# BC28.net
KiCad netlist of a schematic drawn in Altium Designer
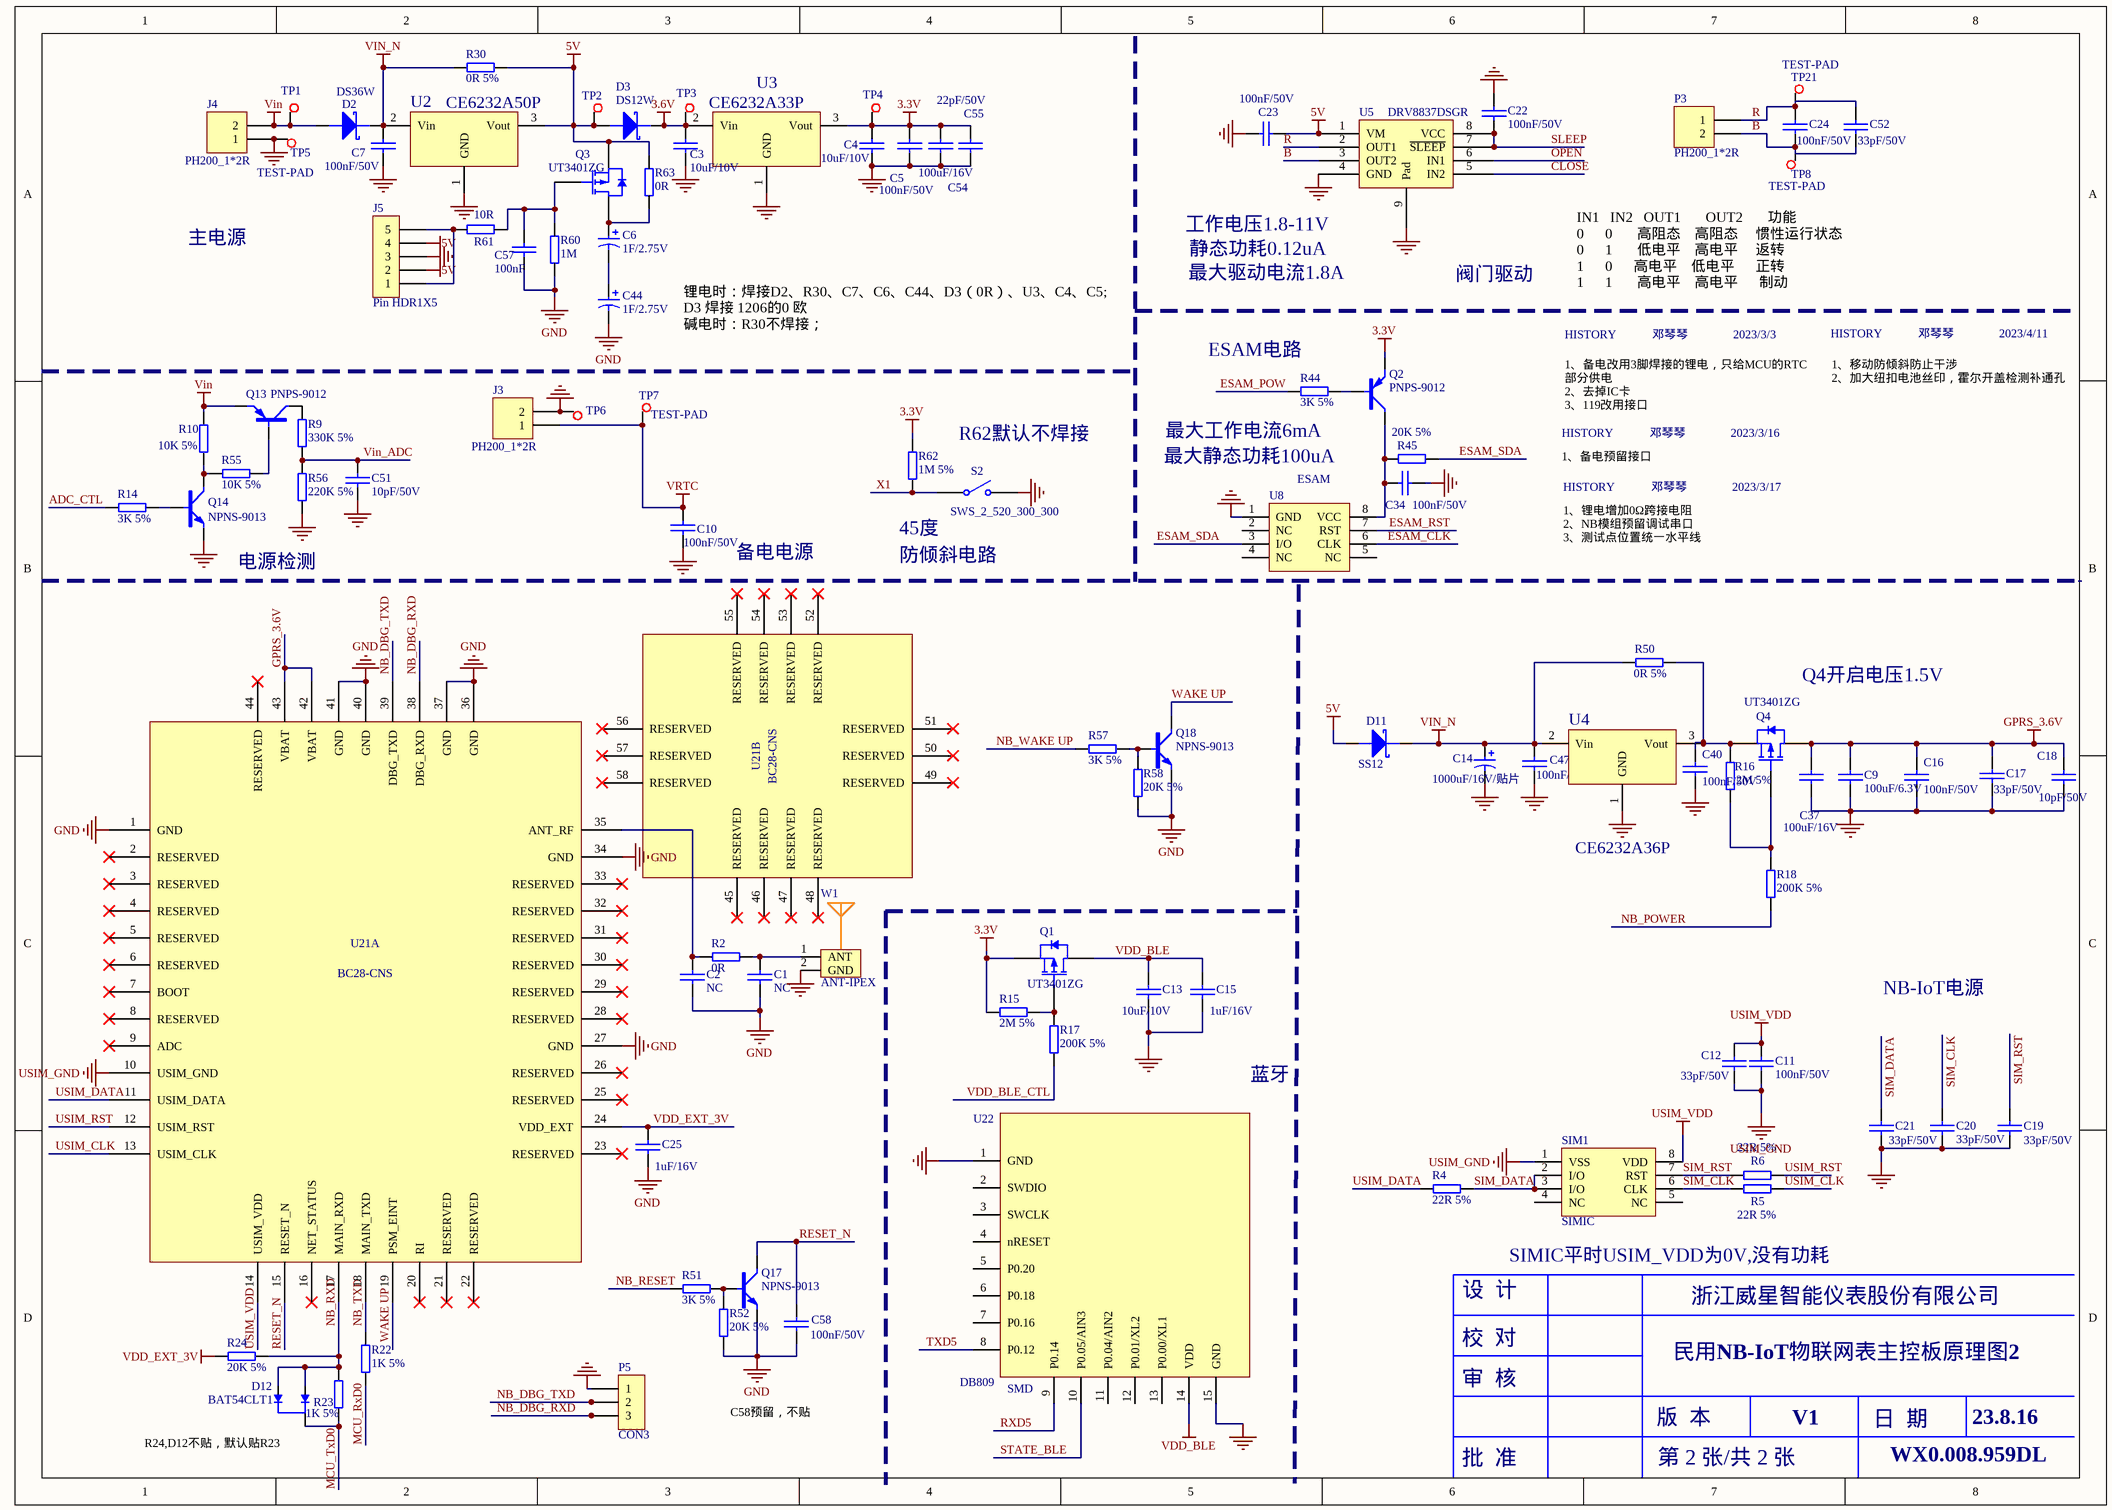
[diagram p0: BC28安全模组.SchDoc]

(export (version "E")
  (design (tool "Eeschema 10.0.6"))
  (components
    (comp (ref "C1")
      (value "NC")
      (footprint "CAP0603")
      (description "12P,50 V,±5%,0603,国巨,CC0603JRNPO9BN12")
      (fields (field (name "PART NUMBER") "101020103-0005"))
      (libsource (lib "Database_Libs2") (part "CC03JPO9_12P"))
    )
    (comp (ref "C2")
      (value "NC")
      (footprint "CAP0603")
      (description "12P,50 V,±5%,0603,国巨,CC0603JRNPO9BN12")
      (fields (field (name "PART NUMBER") "101020103-0005"))
      (libsource (lib "Database_Libs2") (part "CC03JPO9_12P"))
    )
    (comp (ref "C3")
      (value "10uF/10V")
      (footprint "CAP0603")
      (description "106pF,10 V,±10%,0603,村田,GRM188R61A106KE47D")
      (fields (field (name "PART NUMBER") "101020103-0026"))
      (libsource (lib "Database_Libs2") (part "CC03K5R6_10U"))
    )
    (comp (ref "C4")
      (value "10uF/10V")
      (footprint "CAP0603")
      (description "106pF,10 V,±10%,0603,村田,GRM188R61A106KE47D")
      (fields (field (name "PART NUMBER") "101020103-0026"))
      (libsource (lib "Database_Libs2") (part "CC03K5R6_10U"))
    )
    (comp (ref "C5")
      (value "100nF/50V")
      (footprint "CAP0603")
      (description "104pF,50 V,±10%,0603,国巨,CC0603KRX7R9BB104")
      (fields (field (name "PART NUMBER") "101020103-0021"))
      (libsource (lib "Database_Libs2") (part "CC03K7R9_100N"))
    )
    (comp (ref "C6")
      (value "1F/2.75V")
      (footprint "CAPPC_350_800_1600R")
      (description "1F,2.75 V,-20%~+20%,8mm*16mm,红宝石,2.7 DMC 1 M MY4 8X16")
      (fields (field (name "PART NUMBER") "1010202-0015"))
      (libsource (lib "Database_Libs2") (part "CALM3MRDMC_1F"))
    )
    (comp (ref "C7")
      (value "100nF/50V")
      (footprint "CAP0603")
      (description "104pF,50 V,±10%,0603,国巨,CC0603KRX7R9BB104")
      (fields (field (name "PART NUMBER") "101020103-0021"))
      (libsource (lib "Database_Libs2") (part "CC03K7R9_100N"))
    )
    (comp (ref "C9")
      (value "100uF/6.3V")
      (footprint "GRM1206")
      (description "100uF,6.3 V,±20%,1206,村田,GRM31CR60J107ME39L")
      (fields (field (name "PART NUMBER") "101020101-0020"))
      (libsource (lib "Database_Libs2") (part "CC06M5R5_107P"))
    )
    (comp (ref "C10")
      (value "100nF/50V")
      (footprint "CAP0603")
      (description "104pF,50 V,±10%,0603,国巨,CC0603KRX7R9BB104")
      (fields (field (name "PART NUMBER") "101020103-0021"))
      (libsource (lib "Database_Libs2") (part "CC03K7R9_100N"))
    )
    (comp (ref "C11")
      (value "100nF/50V")
      (footprint "CAP0603")
      (description "104pF,50 V,±10%,0603,国巨,CC0603KRX7R9BB104")
      (fields (field (name "PART NUMBER") "101020103-0021"))
      (libsource (lib "Database_Libs2") (part "CC03K7R9_100N"))
    )
    (comp (ref "C12")
      (value "33pF/50V")
      (footprint "CAP0603")
      (description "33pF,50 V,±10%,0603,国巨,CC0603KRNPO9BN33")
      (fields (field (name "PART NUMBER") "101020103-0027"))
      (libsource (lib "Database_Libs2") (part "CC03KPO9_33P"))
    )
    (comp (ref "C13")
      (value "10uF/10V")
      (footprint "CAP0603")
      (description "106pF,10 V,±10%,0603,村田,GRM188R61A106KE47D")
      (fields (field (name "PART NUMBER") "101020103-0026"))
      (libsource (lib "Database_Libs2") (part "CC03K5R6_10U"))
    )
    (comp (ref "C14")
      (value "1000uF/16V/贴片")
      (footprint "CAP-SMD_BD10.0-L10.3-W10.3-FD")
      (description "1000UF,16V,±20%,贴片10*10.2MM,深圳市三炎科电子科技有限公司,16V1000UF")
      (fields (field (name "PART NUMBER") "1010203-0026"))
      (libsource (lib "Database_Libs2") (part "CAL7MRZLH_1000U_R"))
    )
    (comp (ref "C15")
      (value "1uF/16V")
      (footprint "CAP0603")
      (description "105pF,16 V,±10%,0603,国巨,CC0603KRX7R7BB105")
      (fields (field (name "PART NUMBER") "101020103-0003"))
      (libsource (lib "Database_Libs2") (part "CC03K7R7_1U"))
    )
    (comp (ref "C16")
      (value "100nF/50V")
      (footprint "CAP0603")
      (description "104pF,50 V,±10%,0603,国巨,CC0603KRX7R9BB104")
      (fields (field (name "PART NUMBER") "101020103-0021"))
      (libsource (lib "Database_Libs2") (part "CC03K7R9_100N"))
    )
    (comp (ref "C17")
      (value "33pF/50V")
      (footprint "CAP0603")
      (description "33pF,50 V,±10%,0603,国巨,CC0603KRNPO9BN33")
      (fields (field (name "PART NUMBER") "101020103-0027"))
      (libsource (lib "Database_Libs2") (part "CC03KPO9_33P"))
    )
    (comp (ref "C18")
      (value "10pF/50V")
      (footprint "CAP0603")
      (description "10pF,50 V,±5%,0603,X7R,国巨,CC0603JRNPO9BN100")
      (fields (field (name "PART NUMBER") "101020103-0014"))
      (libsource (lib "Database_Libs2") (part "CC03JPO9_10P"))
    )
    (comp (ref "C19")
      (value "33pF/50V")
      (footprint "CAP0603")
      (description "33pF,50 V,±10%,0603,国巨,CC0603KRNPO9BN33")
      (fields (field (name "PART NUMBER") "101020103-0027"))
      (libsource (lib "Database_Libs2") (part "CC03KPO9_33P"))
    )
    (comp (ref "C20")
      (value "33pF/50V")
      (footprint "CAP0603")
      (description "33pF,50 V,±10%,0603,国巨,CC0603KRNPO9BN33")
      (fields (field (name "PART NUMBER") "101020103-0027"))
      (libsource (lib "Database_Libs2") (part "CC03KPO9_33P"))
    )
    (comp (ref "C21")
      (value "33pF/50V")
      (footprint "CAP0603")
      (description "33pF,50 V,±10%,0603,国巨,CC0603KRNPO9BN33")
      (fields (field (name "PART NUMBER") "101020103-0027"))
      (libsource (lib "Database_Libs2") (part "CC03KPO9_33P"))
    )
    (comp (ref "C22")
      (value "100nF/50V")
      (footprint "CAP0603")
      (description "104pF,50 V,±10%,0603,国巨,CC0603KRX7R9BB104")
      (fields (field (name "PART NUMBER") "101020103-0021"))
      (libsource (lib "Database_Libs2") (part "CC03K7R9_100N"))
    )
    (comp (ref "C23")
      (value "100nF/50V")
      (footprint "CAP0603")
      (description "104pF,50 V,±10%,0603,国巨,CC0603KRX7R9BB104")
      (fields (field (name "PART NUMBER") "101020103-0021"))
      (libsource (lib "Database_Libs2") (part "CC03K7R9_100N"))
    )
    (comp (ref "C24")
      (value "100nF/50V")
      (footprint "CAP0603")
      (description "104pF,50 V,±10%,0603,国巨,CC0603KRX7R9BB104")
      (fields (field (name "PART NUMBER") "101020103-0021"))
      (libsource (lib "Database_Libs2") (part "CC03K7R9_100N"))
    )
    (comp (ref "C25")
      (value "1uF/16V")
      (footprint "CAP0603")
      (description "105pF,16 V,±10%,0603,国巨,CC0603KRX7R7BB105")
      (fields (field (name "PART NUMBER") "101020103-0003"))
      (libsource (lib "Database_Libs2") (part "CC03K7R7_1U"))
    )
    (comp (ref "C34")
      (value "100nF/50V")
      (footprint "CAP0603")
      (description "104pF,50 V,±10%,0603,国巨,CC0603KRX7R9BB104")
      (fields (field (name "PART NUMBER") "101020103-0021"))
      (libsource (lib "Database_Libs2") (part "CC03K7R9_100N"))
    )
    (comp (ref "C37")
      (value "100uF/16V")
      (footprint "GRM31CR60J107ME39L")
      (libsource (lib "Database_Libs2") (part "CC06KPO7_106P"))
    )
    (comp (ref "C40")
      (value "100nF/50V")
      (footprint "CAP0603")
      (description "104pF,50 V,±10%,0603,国巨,CC0603KRX7R9BB104")
      (fields (field (name "PART NUMBER") "101020103-0021"))
      (libsource (lib "Database_Libs2") (part "CC03K7R9_100N"))
    )
    (comp (ref "C44")
      (value "1F/2.75V")
      (footprint "CAPPC_350_800_1600R")
      (description "1F,2.75 V,-20%~+20%,8mm*16mm,红宝石,2.7 DMC 1 M MY4 8X16")
      (fields (field (name "PART NUMBER") "1010202-0015"))
      (libsource (lib "Database_Libs2") (part "CALM3MRDMC_1F"))
    )
    (comp (ref "C47")
      (value "100nF/50V")
      (footprint "CAP0603")
      (description "104pF,50 V,±10%,0603,国巨,CC0603KRX7R9BB104")
      (fields (field (name "PART NUMBER") "101020103-0021"))
      (libsource (lib "Database_Libs2") (part "CC03K7R9_100N"))
    )
    (comp (ref "C51")
      (value "10pF/50V")
      (footprint "CAP0603")
      (description "10pF,50 V,±5%,0603,X7R,国巨,CC0603JRNPO9BN100")
      (fields (field (name "PART NUMBER") "101020103-0014"))
      (libsource (lib "Database_Libs2") (part "CC03JPO9_10P"))
    )
    (comp (ref "C52")
      (value "33pF/50V")
      (footprint "CAP0603")
      (description "104pF,50 V,±10%,0603,国巨,CC0603KRX7R9BB104")
      (fields (field (name "PART NUMBER") "101020103-0021"))
      (libsource (lib "Database_Libs2") (part "CC03K7R9_100N"))
    )
    (comp (ref "C54")
      (value "100uF/16V")
      (footprint "GRM31CR60J107ME39L")
      (description "100u,16 V,±10%,1206,国巨,CC1206KRNPO7BN106P")
      (libsource (lib "Database_Libs2") (part "CC06KPO7_106P"))
    )
    (comp (ref "C55")
      (value "22pF/50V")
      (footprint "CAP0603")
      (description "22pF,50 V,±5%,0603,国巨,CC0603JRNPO9BN22")
      (fields (field (name "PART NUMBER") "101020103-0009"))
      (libsource (lib "Database_Libs2") (part "CC03JPO9_22P"))
    )
    (comp (ref "C57")
      (value "100nF")
      (footprint "CAP0603")
      (description "无极性电容")
      (libsource (lib "CBB_Lib_SCH") (part "CAP"))
    )
    (comp (ref "C58")
      (value "100nF/50V")
      (footprint "CAP0603")
      (description "104pF,50 V,±10%,0603,国巨,CC0603KRX7R9BB104")
      (fields (field (name "PART NUMBER") "101020103-0021"))
      (libsource (lib "Database_Libs2") (part "CC03K7R9_100N"))
    )
    (comp (ref "D2")
      (value "DS36W")
      (footprint "SOD-123FL")
      (description "DS36W,SOD123-FL,3 A,42 V,60 V,浙江领晨科技有限公司,DS36W")
      (fields (field (name "PART NUMBER") "101040101-0055"))
      (libsource (lib "Database_Libs2") (part "02_DS12W"))
    )
    (comp (ref "D3")
      (value "DS12W")
      (footprint "SOD-123FL")
      (description "DS12W,SOD-123FL,1 A,0.55 V,20 V,领晨科技,DS12W")
      (fields (field (name "PART NUMBER") "101040101-0048"))
      (libsource (lib "Database_Libs2") (part "02_DS12W"))
    )
    (comp (ref "D11")
      (value "SS12")
      (footprint "DO-214AC")
      (description "SS12,DO-214AC,1 A,0.55 V,20 V,昶鑫,SS12")
      (fields (field (name "PART NUMBER") "101040101-0009"))
      (libsource (lib "Database_Libs2") (part "02_SS12"))
    )
    (comp (ref "D12")
      (value "BAT54CLT1")
      (footprint "SOT-23")
      (description "BAT54CLT1，SOT23-3,SOT23-3,0.2 A,0.8 V,30 V,安森美,BAT54CLT1")
      (fields (field (name "PART NUMBER") "101040101-0038"))
      (libsource (lib "Database_Libs2") (part "02_BAT54CLT1"))
    )
    (comp (ref "J3")
      (value "PH200_1*2R")
      (footprint "BAT-DIP-2")
      (description "2.0-2AW,直插弯座，2PIN，脚间距2mm，带防翘起,公头,单排,2.0-2AW;直插弯座，2PIN,脚间距2mm，带防翘起")
      (fields (field (name "PART NUMBER") "1010902-0105"))
      (libsource (lib "Database_Libs2") (part "PH200_1*2R"))
    )
    (comp (ref "J4")
      (value "PH200_1*2R")
      (footprint "PH200_1*2R_BAT")
      (description "2.0-2AW,直插弯座，2PIN，脚间距2mm，带防翘起,公头,单排,2.0-2AW;直插弯座，2PIN,脚间距2mm，带防翘起")
      (fields (field (name "PART NUMBER") "1010902-0105"))
      (libsource (lib "Database_Libs2") (part "PH200_1*2R"))
    )
    (comp (ref "J5")
      (value "Pin HDR1X5")
      (footprint "Pin HDR1X5/2.54mm-S")
      (libsource (lib "排针") (part "Pin HDR1X5"))
    )
    (comp (ref "P3")
      (value "PH200_1*2R")
      (footprint "PH200_1*2R")
      (description "2.0-2AW,直插弯座，2PIN，脚间距2mm，带防翘起,公头,单排,2.0-2AW;直插弯座，2PIN,脚间距2mm，带防翘起")
      (fields (field (name "PART NUMBER") "1010902-0105"))
      (libsource (lib "") (part "PH200_1*2R_1"))
    )
    (comp (ref "P5")
      (value "CON3")
      (footprint "SIP-3")
      (description "Connector")
      (libsource (lib "Miscellaneous Devices") (part "CON3"))
    )
    (comp (ref "Q1")
      (value "UT3401ZG")
      (footprint "SOT-23")
      (description "UT3401ZG,P-MOS,SOT-23,UTC,UT3401ZG")
      (fields (field (name "PART NUMBER") "101040201-0013"))
      (libsource (lib "Database_Libs2") (part "03_P-UT3401ZG"))
    )
    (comp (ref "Q2")
      (value "PNPS-9012")
      (footprint "SOT-23")
      (description "9012,PNP,SOT-23,JCET;长电,S9012")
      (fields (field (name "PART NUMBER") "101040201-0001"))
      (libsource (lib "Database_Libs2") (part "03_PNPS-9012"))
    )
    (comp (ref "Q3")
      (value "UT3401ZG")
      (footprint "SOT-23")
      (description "UT3401ZG,P-MOS,SOT-23,UTC,UT3401ZG")
      (fields (field (name "PART NUMBER") "101040201-0013"))
      (libsource (lib "Database_Libs2") (part "03_P-UT3401ZG"))
    )
    (comp (ref "Q4")
      (value "UT3401ZG")
      (footprint "SOT-23")
      (description "UT3401ZG,P-MOS,SOT-23,UTC,UT3401ZG")
      (fields (field (name "PART NUMBER") "101040201-0013"))
      (libsource (lib "Database_Libs2") (part "03_P-UT3401ZG"))
    )
    (comp (ref "Q13")
      (value "PNPS-9012")
      (footprint "SOT-23")
      (description "9012,PNP,SOT-23,JCET;长电,S9012")
      (fields (field (name "PART NUMBER") "101040201-0001"))
      (libsource (lib "Database_Libs2") (part "03_PNPS-9012"))
    )
    (comp (ref "Q14")
      (value "NPNS-9013")
      (footprint "SOT-23")
      (description "9013,NPN,SOT-23,长电,S9013")
      (fields (field (name "PART NUMBER") "101040201-0002"))
      (libsource (lib "Database_Libs2") (part "03_NPNS-9013"))
    )
    (comp (ref "Q17")
      (value "NPNS-9013")
      (footprint "SOT-23")
      (description "9013,NPN,SOT-23,长电,S9013")
      (fields (field (name "PART NUMBER") "101040201-0002"))
      (libsource (lib "Database_Libs2") (part "03_NPNS-9013"))
    )
    (comp (ref "Q18")
      (value "NPNS-9013")
      (footprint "SOT-23")
      (description "9013,NPN,SOT-23,长电,S9013")
      (fields (field (name "PART NUMBER") "101040201-0002"))
      (libsource (lib "Database_Libs2") (part "03_NPNS-9013"))
    )
    (comp (ref "R2")
      (value "0R")
      (footprint "RES0603")
      (fields (field (name "PART NUMBER") "101010103-0001"))
      (libsource (lib "Database_Libs2") (part "RC03J_0R"))
    )
    (comp (ref "R4")
      (value "22R 5%")
      (footprint "RES0603")
      (description "国巨,±5%,0603,,155 ℃,-55 ℃,RC0603JR-0722RL,无铅,200 ppm/℃,1/10W,,22欧")
      (fields (field (name "PART NUMBER") "101010103-0009"))
      (libsource (lib "Database_Libs2") (part "RC03J_22R"))
    )
    (comp (ref "R5")
      (value "22R 5%")
      (footprint "RES0603")
      (description "国巨,±5%,0603,,155 ℃,-55 ℃,RC0603JR-0722RL,无铅,200 ppm/℃,1/10W,,22欧")
      (fields (field (name "PART NUMBER") "101010103-0009"))
      (libsource (lib "Database_Libs2") (part "RC03J_22R"))
    )
    (comp (ref "R6")
      (value "22R 5%")
      (footprint "RES0603")
      (description "国巨,±5%,0603,,155 ℃,-55 ℃,RC0603JR-0722RL,无铅,200 ppm/℃,1/10W,,22欧")
      (fields (field (name "PART NUMBER") "101010103-0009"))
      (libsource (lib "Database_Libs2") (part "RC03J_22R"))
    )
    (comp (ref "R9")
      (value "330K 5%")
      (footprint "RES0603")
      (description "330K,±5%,1/10W,0603,国巨,RC0603JR-07330KL")
      (fields (field (name "PART NUMBER") "101010103-0066"))
      (libsource (lib "Database_Libs2") (part "RC03J_330K"))
    )
    (comp (ref "R10")
      (value "10K 5%")
      (footprint "RES0603")
      (description "国巨,±5%,0603,,155 ℃,-55 ℃,RC0603JR-0710KL,无铅,200 ppm/℃,1/10W,,10K")
      (fields (field (name "PART NUMBER") "101010103-0003"))
      (libsource (lib "Database_Libs2") (part "RC03J_10K"))
    )
    (comp (ref "R14")
      (value "3K 5%")
      (footprint "RES0603")
      (description "国巨,±5%,0603,,155 ℃,-55 ℃,RC0603JR-073KL,无铅,100 ppm/℃,1/10W,,3K")
      (fields (field (name "PART NUMBER") "101010103-0006"))
      (libsource (lib "Database_Libs2") (part "RC03J_3K"))
    )
    (comp (ref "R15")
      (value "2M 5%")
      (footprint "RES0603")
      (description "10K±5%,1/10W,0603")
      (fields (field (name "PART NUMBER") "101010103-0003"))
      (libsource (lib "Database_Libs1") (part "RC03JF_10K"))
    )
    (comp (ref "R16")
      (value "2M 5%")
      (footprint "RES0603")
      (description "国巨,±5%,0603,,155 ℃,-55 ℃,RC0603JR-072ML,含铅,100 ppm/℃,1/10W,,2M")
      (fields (field (name "PART NUMBER") "101010103-0025"))
      (libsource (lib "Database_Libs2") (part "RC03J_2M"))
    )
    (comp (ref "R17")
      (value "200K 5%")
      (footprint "RES0603")
      (description "10K±5%,1/10W,0603")
      (fields (field (name "PART NUMBER") "101010103-0003"))
      (libsource (lib "Database_Libs1") (part "RC03JF_10K"))
    )
    (comp (ref "R18")
      (value "200K 5%")
      (footprint "RES0603")
      (description "200K,±5%,1/10W,0603,国巨,RC0603JR-07200KL")
      (fields (field (name "PART NUMBER") "101010103-0034"))
      (libsource (lib "Database_Libs2") (part "RC03J_200K"))
    )
    (comp (ref "R22")
      (value "1K 5%")
      (footprint "RES0603")
      (description "220K,±5%,1/10W,0603,国巨,RC0603JR-07220KL")
      (fields (field (name "PART NUMBER") "101010103-0044"))
      (libsource (lib "Database_Libs2") (part "RC03J_220K"))
    )
    (comp (ref "R23")
      (value "1K 5%")
      (footprint "RES0603")
      (description "220K,±5%,1/10W,0603,国巨,RC0603JR-07220KL")
      (fields (field (name "PART NUMBER") "101010103-0044"))
      (libsource (lib "Database_Libs2") (part "RC03J_220K"))
    )
    (comp (ref "R24")
      (value "20K 5%")
      (footprint "RES0603")
      (description "国巨,±5%,0603,,155 ℃,-55 ℃,RC0603JR-0720KL,无铅,200 ppm/℃,1/10W,,20K")
      (fields (field (name "PART NUMBER") "101010103-0004"))
      (libsource (lib "Database_Libs2") (part "RC03J_20K"))
    )
    (comp (ref "R30")
      (value "0R 5%")
      (footprint "RES1206")
      (description "0Ω,±5%,1/4W,1206,国巨,RC1206JR-070RL")
      (fields (field (name "PART NUMBER") "101010101-0013"))
      (libsource (lib "Database_Libs2") (part "RC06J_0R"))
    )
    (comp (ref "R44")
      (value "3K 5%")
      (footprint "RES0603")
      (description "国巨,±5%,0603,,155 ℃,-55 ℃,RC0603JR-0710KL,无铅,200 ppm/℃,1/10W,,10K")
      (fields (field (name "PART NUMBER") "101010103-0003"))
      (libsource (lib "Database_Libs2") (part "RC03J_10K"))
    )
    (comp (ref "R45")
      (value "20K 5%")
      (footprint "RES0603")
      (description "国巨,±5%,0603,,155 ℃,-55 ℃,RC0603JR-0720KL,无铅,200 ppm/℃,1/10W,,20K")
      (fields (field (name "PART NUMBER") "101010103-0004"))
      (libsource (lib "Database_Libs2") (part "RC03J_20K"))
    )
    (comp (ref "R50")
      (value "0R 5%")
      (footprint "RES1206")
      (description "0Ω,±5%,1/4W,1206,国巨,RC1206JR-070RL")
      (fields (field (name "PART NUMBER") "101010101-0013"))
      (libsource (lib "Database_Libs2") (part "RC06J_0R"))
    )
    (comp (ref "R51")
      (value "3K 5%")
      (footprint "RES0603")
      (description "220K,±5%,1/10W,0603,国巨,RC0603JR-07220KL")
      (fields (field (name "PART NUMBER") "101010103-0044"))
      (libsource (lib "Database_Libs2") (part "RC03J_220K"))
    )
    (comp (ref "R52")
      (value "20K 5%")
      (footprint "RES0603")
      (description "220K,±5%,1/10W,0603,国巨,RC0603JR-07220KL")
      (fields (field (name "PART NUMBER") "101010103-0044"))
      (libsource (lib "Database_Libs2") (part "RC03J_220K"))
    )
    (comp (ref "R55")
      (value "10K 5%")
      (footprint "RES0603")
      (description "国巨,±5%,0603,,155 ℃,-55 ℃,RC0603JR-0710KL,无铅,200 ppm/℃,1/10W,,10K")
      (fields (field (name "PART NUMBER") "101010103-0003"))
      (libsource (lib "Database_Libs2") (part "RC03J_10K"))
    )
    (comp (ref "R56")
      (value "220K 5%")
      (footprint "RES0603")
      (description "220K,±5%,1/10W,0603,国巨,RC0603JR-07220KL")
      (fields (field (name "PART NUMBER") "101010103-0044"))
      (libsource (lib "Database_Libs2") (part "RC03J_220K"))
    )
    (comp (ref "R57")
      (value "3K 5%")
      (footprint "RES0603")
      (description "220K,±5%,1/10W,0603,国巨,RC0603JR-07220KL")
      (fields (field (name "PART NUMBER") "101010103-0044"))
      (libsource (lib "Database_Libs2") (part "RC03J_220K"))
    )
    (comp (ref "R58")
      (value "20K 5%")
      (footprint "RES0603")
      (description "220K,±5%,1/10W,0603,国巨,RC0603JR-07220KL")
      (fields (field (name "PART NUMBER") "101010103-0044"))
      (libsource (lib "Database_Libs2") (part "RC03J_220K"))
    )
    (comp (ref "R60")
      (value "1M")
      (footprint "Resistor_WX:RES0603")
      (libsource (lib "CBB_Lib_SCH") (part "RES"))
    )
    (comp (ref "R61") (value "10R") (footprint "RES0603") (libsource (lib "CBB_Lib_SCH") (part "RES")))
    (comp (ref "R62")
      (value "1M 5%")
      (footprint "RES0603")
      (description "国巨,±5%,0603,,155 ℃,-55 ℃,RC0603JR-071ML,无铅,200 ppm/℃,1/10W,,1M")
      (fields (field (name "PART NUMBER") "101010103-0002"))
      (libsource (lib "Database_Libs2") (part "RC03J_1M"))
    )
    (comp (ref "R63")
      (value "0R")
      (footprint "Resistor_WX:RES1206")
      (libsource (lib "CBB_Lib_SCH") (part "RES"))
    )
    (comp (ref "S2")
      (value "SWS_2_520_300_300")
      (footprint "SWS_2_520_300")
      (description "CSX-SEN-645B,垂直45°开关转换,3*5.2mm,360°任意方位倾斜检测,深圳市成晟科技有限公司")
      (fields (field (name "PART NUMBER") "1011001-0051"))
      (libsource (lib "Database_Libs2") (part "07_SWS_2_520_300_300"))
    )
    (comp (ref "SIM1")
      (value "SIMIC")
      (footprint "SIMIC")
      (description "SIMIC虚拟器件")
      (fields (field (name "PART NUMBER") "AD_XN_SIMIC_01"))
      (libsource (lib "Database_Libs2") (part "05_SIMIC"))
    )
    (comp (ref "TP1")
      (value "TEST-PAD")
      (footprint "TEST-PAD")
      (description "单面焊盘测试点")
      (fields (field (name "PART NUMBER") "AD_WXHJ_TEST-PAD_01"))
      (libsource (lib "Database_Libs2") (part "TEST-PAD"))
    )
    (comp (ref "TP2")
      (value "TEST-PAD")
      (footprint "TEST-PAD")
      (description "单面焊盘测试点")
      (fields (field (name "PART NUMBER") "AD_WXHJ_TEST-PAD_01"))
      (libsource (lib "Database_Libs2") (part "TEST-PAD"))
    )
    (comp (ref "TP3")
      (value "TEST-PAD")
      (footprint "TEST-PAD")
      (description "单面焊盘测试点")
      (fields (field (name "PART NUMBER") "AD_WXHJ_TEST-PAD_01"))
      (libsource (lib "Database_Libs2") (part "TEST-PAD"))
    )
    (comp (ref "TP4")
      (value "TEST-PAD")
      (footprint "TEST-PAD")
      (description "单面焊盘测试点")
      (fields (field (name "PART NUMBER") "AD_WXHJ_TEST-PAD_01"))
      (libsource (lib "Database_Libs2") (part "TEST-PAD"))
    )
    (comp (ref "TP5")
      (value "TEST-PAD")
      (footprint "TEST-PAD")
      (description "单面焊盘测试点")
      (fields (field (name "PART NUMBER") "AD_WXHJ_TEST-PAD_01"))
      (libsource (lib "Database_Libs2") (part "TEST-PAD"))
    )
    (comp (ref "TP6")
      (value "TEST-PAD")
      (footprint "TEST-PAD")
      (description "单面焊盘测试点")
      (fields (field (name "PART NUMBER") "AD_WXHJ_TEST-PAD_01"))
      (libsource (lib "Database_Libs2") (part "TEST-PAD"))
    )
    (comp (ref "TP7")
      (value "TEST-PAD")
      (footprint "TEST-PAD")
      (description "单面焊盘测试点")
      (fields (field (name "PART NUMBER") "AD_WXHJ_TEST-PAD_01"))
      (libsource (lib "Database_Libs2") (part "TEST-PAD"))
    )
    (comp (ref "TP8")
      (value "TEST-PAD")
      (footprint "TEST-PAD")
      (description "单面焊盘测试点")
      (fields (field (name "PART NUMBER") "AD_WXHJ_TEST-PAD_01"))
      (libsource (lib "Database_Libs2") (part "TEST-PAD"))
    )
    (comp (ref "TP21")
      (value "TEST-PAD")
      (footprint "TEST-PAD")
      (description "单面焊盘测试点")
      (fields (field (name "PART NUMBER") "AD_WXHJ_TEST-PAD_01"))
      (libsource (lib "Database_Libs2") (part "TEST-PAD"))
    )
    (comp (ref "U2")
      (value "CE6232A50P")
      (footprint "SOT-89")
      (fields (field (name "PART NUMBER") "1010503-0013"))
      (libsource (lib "Database_Libs2") (part "02_S-1206B50-U3"))
    )
    (comp (ref "U3")
      (value "CE6232A33P")
      (footprint "SOT-89")
      (fields (field (name "PART NUMBER") "1010503-0002"))
      (libsource (lib "Database_Libs2") (part "02_S-1206B33-U3T1G"))
    )
    (comp (ref "U4")
      (value "CE6232A36P")
      (footprint "SOT-89")
      (description "CE6232A36P,CE6232A36P,SOT89-3,8 V,1.8 V,0.11 V,3.6 V,600mA,0.8 uA,南京芯力微电子有限公司")
      (fields (field (name "PART NUMBER") "1010503-0031"))
      (libsource (lib "Database_Libs2") (part "02_CE6232A36P"))
    )
    (comp (ref "U5")
      (value "DRV8837DSGR")
      (footprint "S-PWSON-N8")
      (description "DRV8837DSGR,S-PWSON-N8,TI,DRV8837DSGR")
      (fields (field (name "PART NUMBER") "101050101-0060"))
      (libsource (lib "Database_Libs2") (part "07_DRV8837DSGR"))
    )
    (comp (ref "U8")
      (value "ESAM")
      (footprint "SOP-8")
      (description "ESAM虚拟器件")
      (fields (field (name "PART NUMBER") "AD_XN_ESAM_01"))
      (libsource (lib "Database_Libs2") (part "04_ESAM"))
    )
    (comp (ref "U21")
      (value "BC28-CNS")
      (footprint "BC28-CNS")
      (description "BC28-CNS Moudle 58Pin 15.8X17.7mm H2.2mm RO")
      (fields (field (name "MANUFACTURER") "Quectel"))
      (libsource (lib "Chip_WX") (part "BC28-CNS"))
    )
    (comp (ref "U22")
      (value "DB809")
      (footprint "DB809")
      (description "北高智蓝牙模块DB809")
      (fields (field (name "PART NUMBER") "1011402-0194") (field (name "SMD/DIP") "SMD"))
      (libsource (lib "Database_Libs2") (part "01_DB809"))
    )
    (comp (ref "W1")
      (value "ANT-IPEX")
      (footprint "ANT-IPEX")
      (description "IPEX，配GPRS天线转接线")
      (fields (field (name "PART NUMBER") "1010902-0053"))
      (libsource (lib "Database_Libs2") (part "IPEX"))
    )
  )
  (nets
    (net (code "1") (name "/ADC_CTL") (class "Default")
      (node (ref "R14") (pin "1") (pinfunction "1_1") (pintype "passive"))
    )
    (net (code "2") (name "/B") (class "Default")
      (node (ref "C24") (pin "2") (pinfunction "2_2") (pintype "passive"))
      (node (ref "C52") (pin "2") (pinfunction "2_2") (pintype "passive"))
      (node (ref "P3") (pin "2") (pinfunction "2_2") (pintype "passive"))
      (node (ref "TP8") (pin "1") (pinfunction "1_1") (pintype "passive"))
      (node (ref "U5") (pin "3") (pinfunction "OUT2_3") (pintype "passive"))
    )
    (net (code "3") (name "/CLOSE") (class "Default")
      (node (ref "U5") (pin "5") (pinfunction "IN2_5") (pintype "passive"))
    )
    (net (code "4") (name "/ESAM_CLK") (class "Default")
      (node (ref "U8") (pin "6") (pinfunction "CLK_6") (pintype "passive"))
    )
    (net (code "5") (name "/ESAM_POW") (class "Default")
      (node (ref "R44") (pin "1") (pinfunction "1_1") (pintype "passive"))
    )
    (net (code "6") (name "/ESAM_RST") (class "Default")
      (node (ref "U8") (pin "7") (pinfunction "RST_7") (pintype "passive"))
    )
    (net (code "7") (name "/ESAM_SDA") (class "Default")
      (node (ref "R45") (pin "2") (pinfunction "2_2") (pintype "passive"))
      (node (ref "U8") (pin "3") (pinfunction "I/O_3") (pintype "passive"))
    )
    (net (code "8") (name "/MCU_RxD0") (class "Default")
      (node (ref "R22") (pin "1") (pinfunction "1_1") (pintype "passive"))
    )
    (net (code "9") (name "/MCU_TxD0") (class "Default")
      (node (ref "D12") (pin "3") (pinfunction "C_3") (pintype "passive"))
      (node (ref "R23") (pin "2") (pinfunction "2_2") (pintype "passive"))
    )
    (net (code "10") (name "/NB_DBG_RXD") (class "Default")
      (node (ref "P5") (pin "3") (pinfunction "3_3") (pintype "passive"))
      (node (ref "U21") (pin "38") (pinfunction "DBG_RXD_38") (pintype "passive"))
    )
    (net (code "11") (name "/NB_DBG_TXD") (class "Default")
      (node (ref "P5") (pin "2") (pinfunction "2_2") (pintype "passive"))
      (node (ref "U21") (pin "39") (pinfunction "DBG_TXD_39") (pintype "passive"))
    )
    (net (code "12") (name "/NB_POWER") (class "Default")
      (node (ref "R18") (pin "1") (pinfunction "1_1") (pintype "passive"))
    )
    (net (code "13") (name "/NB_RESET") (class "Default")
      (node (ref "R51") (pin "1") (pinfunction "1_1") (pintype "passive"))
    )
    (net (code "14") (name "/NB_RXD") (class "Default")
      (node (ref "D12") (pin "1") (pinfunction "A_1") (pintype "passive"))
      (node (ref "D12") (pin "2") (pinfunction "A_2") (pintype "passive"))
      (node (ref "R23") (pin "1") (pinfunction "1_1") (pintype "passive"))
      (node (ref "R24") (pin "2") (pinfunction "2_2") (pintype "passive"))
      (node (ref "U21") (pin "17") (pinfunction "MAIN_RXD_17") (pintype "passive"))
    )
    (net (code "15") (name "/NB_TXD") (class "Default")
      (node (ref "R22") (pin "2") (pinfunction "2_2") (pintype "passive"))
      (node (ref "U21") (pin "18") (pinfunction "MAIN_TXD_18") (pintype "passive"))
    )
    (net (code "16") (name "/NB_WAKE UP") (class "Default")
      (node (ref "R57") (pin "1") (pinfunction "1_1") (pintype "passive"))
    )
    (net (code "17") (name "/OPEN") (class "Default")
      (node (ref "U5") (pin "6") (pinfunction "IN1_6") (pintype "passive"))
    )
    (net (code "18") (name "/R") (class "Default")
      (node (ref "C24") (pin "1") (pinfunction "1_1") (pintype "passive"))
      (node (ref "C52") (pin "1") (pinfunction "1_1") (pintype "passive"))
      (node (ref "P3") (pin "1") (pinfunction "1_1") (pintype "passive"))
      (node (ref "TP21") (pin "1") (pinfunction "1_1") (pintype "passive"))
      (node (ref "U5") (pin "2") (pinfunction "OUT1_2") (pintype "passive"))
    )
    (net (code "19") (name "/RESET_N") (class "Default")
      (node (ref "C58") (pin "1") (pinfunction "1_1") (pintype "passive"))
      (node (ref "Q17") (pin "3") (pinfunction "C_3") (pintype "passive"))
      (node (ref "U21") (pin "15") (pinfunction "RESET_N_15") (pintype "passive"))
    )
    (net (code "20") (name "/RXD5") (class "Default")
      (node (ref "U22") (pin "9") (pinfunction "P0.14_9") (pintype "passive"))
    )
    (net (code "21") (name "/SIM_CLK") (class "Default")
      (node (ref "C20") (pin "1") (pinfunction "1_1") (pintype "passive"))
      (node (ref "R5") (pin "1") (pinfunction "1_1") (pintype "passive"))
      (node (ref "SIM1") (pin "6") (pinfunction "CLK_6") (pintype "passive"))
    )
    (net (code "22") (name "/SIM_DATA") (class "Default")
      (node (ref "C21") (pin "1") (pinfunction "1_1") (pintype "passive"))
      (node (ref "R4") (pin "2") (pinfunction "2_2") (pintype "passive"))
      (node (ref "SIM1") (pin "2") (pinfunction "I/O_2") (pintype "passive"))
      (node (ref "SIM1") (pin "3") (pinfunction "I/O_3") (pintype "passive"))
    )
    (net (code "23") (name "/SIM_RST") (class "Default")
      (node (ref "C19") (pin "1") (pinfunction "1_1") (pintype "passive"))
      (node (ref "R6") (pin "1") (pinfunction "1_1") (pintype "passive"))
      (node (ref "SIM1") (pin "7") (pinfunction "RST_7") (pintype "passive"))
    )
    (net (code "24") (name "/SLEEP") (class "Default")
      (node (ref "C22") (pin "2") (pinfunction "2_2") (pintype "passive"))
      (node (ref "U5") (pin "7") (pinfunction "~{SLEEP}_7") (pintype "passive"))
      (node (ref "U5") (pin "8") (pinfunction "VCC_8") (pintype "passive"))
    )
    (net (code "25") (name "/STATE_BLE") (class "Default")
      (node (ref "U22") (pin "10") (pinfunction "P0.05/AIN3_10") (pintype "passive"))
    )
    (net (code "26") (name "/TXD5") (class "Default")
      (node (ref "U22") (pin "8") (pinfunction "P0.12_8") (pintype "passive"))
    )
    (net (code "27") (name "/USIM_CLK") (class "Default")
      (node (ref "R5") (pin "2") (pinfunction "2_2") (pintype "passive"))
      (node (ref "U21") (pin "13") (pinfunction "USIM_CLK_13") (pintype "passive"))
    )
    (net (code "28") (name "/USIM_DATA") (class "Default")
      (node (ref "R4") (pin "1") (pinfunction "1_1") (pintype "passive"))
      (node (ref "U21") (pin "11") (pinfunction "USIM_DATA_11") (pintype "passive"))
    )
    (net (code "29") (name "/USIM_RST") (class "Default")
      (node (ref "R6") (pin "2") (pinfunction "2_2") (pintype "passive"))
      (node (ref "U21") (pin "12") (pinfunction "USIM_RST_12") (pintype "passive"))
    )
    (net (code "30") (name "/VDD_BLE_CTL") (class "Default")
      (node (ref "R17") (pin "1") (pinfunction "1_1") (pintype "passive"))
    )
    (net (code "31") (name "/Vin_ADC") (class "Default")
      (node (ref "C51") (pin "2") (pinfunction "2_2") (pintype "passive"))
      (node (ref "R56") (pin "1") (pinfunction "1_1") (pintype "passive"))
      (node (ref "R9") (pin "2") (pinfunction "2_2") (pintype "passive"))
    )
    (net (code "32") (name "/WAKE UP") (class "Default")
      (node (ref "Q18") (pin "3") (pinfunction "C_3") (pintype "passive"))
      (node (ref "U21") (pin "19") (pinfunction "PSM_EINT_19") (pintype "passive"))
    )
    (net (code "33") (name "/X1") (class "Default")
      (node (ref "R62") (pin "1") (pinfunction "1_1") (pintype "passive"))
      (node (ref "S2") (pin "1") (pintype "passive"))
    )
    (net (code "34") (name "3.3V") (class "Default")
      (node (ref "C4") (pin "1") (pinfunction "1_1") (pintype "passive"))
      (node (ref "C5") (pin "1") (pinfunction "1_1") (pintype "passive"))
      (node (ref "C54") (pin "1") (pinfunction "1_1") (pintype "passive"))
      (node (ref "C55") (pin "1") (pinfunction "1_1") (pintype "passive"))
      (node (ref "Q1") (pin "2") (pinfunction "S_2") (pintype "passive"))
      (node (ref "Q2") (pin "2") (pinfunction "E_2") (pintype "passive"))
      (node (ref "R15") (pin "1") (pinfunction "1_1") (pintype "passive"))
      (node (ref "R62") (pin "2") (pinfunction "2_2") (pintype "passive"))
      (node (ref "TP4") (pin "1") (pinfunction "1_1") (pintype "passive"))
      (node (ref "U3") (pin "3") (pinfunction "Vout_3") (pintype "passive"))
    )
    (net (code "35") (name "3.6V") (class "Default")
      (node (ref "C3") (pin "1") (pinfunction "1_1") (pintype "passive"))
      (node (ref "D3") (pin "2") (pinfunction "2_2") (pintype "passive"))
      (node (ref "TP3") (pin "1") (pinfunction "1_1") (pintype "passive"))
      (node (ref "U3") (pin "2") (pinfunction "Vin_2") (pintype "passive"))
    )
    (net (code "36") (name "5V") (class "Default")
      (node (ref "C23") (pin "2") (pinfunction "2_2") (pintype "passive"))
      (node (ref "D11") (pin "1") (pinfunction "1_1") (pintype "passive"))
      (node (ref "D3") (pin "1") (pinfunction "1_1") (pintype "passive"))
      (node (ref "J5") (pin "2") (pinfunction "2_2") (pintype "passive"))
      (node (ref "J5") (pin "4") (pinfunction "4_4") (pintype "passive"))
      (node (ref "Q3") (pin "2") (pinfunction "S_2") (pintype "passive"))
      (node (ref "R30") (pin "2") (pinfunction "2_2") (pintype "passive"))
      (node (ref "R63") (pin "1") (pintype "passive"))
      (node (ref "TP2") (pin "1") (pinfunction "1_1") (pintype "passive"))
      (node (ref "U2") (pin "3") (pinfunction "Vout_3") (pintype "passive"))
      (node (ref "U5") (pin "1") (pinfunction "VM_1") (pintype "passive"))
    )
    (net (code "37") (name "GND") (class "Default")
      (node (ref "C1") (pin "1") (pinfunction "1_1") (pintype "passive"))
      (node (ref "C10") (pin "2") (pinfunction "2_2") (pintype "passive"))
      (node (ref "C13") (pin "2") (pinfunction "2_2") (pintype "passive"))
      (node (ref "C14") (pin "2") (pinfunction "2_2") (pintype "passive"))
      (node (ref "C15") (pin "2") (pinfunction "2_2") (pintype "passive"))
      (node (ref "C16") (pin "2") (pinfunction "2_2") (pintype "passive"))
      (node (ref "C17") (pin "2") (pinfunction "2_2") (pintype "passive"))
      (node (ref "C18") (pin "2") (pinfunction "2_2") (pintype "passive"))
      (node (ref "C19") (pin "2") (pinfunction "2_2") (pintype "passive"))
      (node (ref "C2") (pin "1") (pinfunction "1_1") (pintype "passive"))
      (node (ref "C20") (pin "2") (pinfunction "2_2") (pintype "passive"))
      (node (ref "C21") (pin "2") (pinfunction "2_2") (pintype "passive"))
      (node (ref "C22") (pin "1") (pinfunction "1_1") (pintype "passive"))
      (node (ref "C23") (pin "1") (pinfunction "1_1") (pintype "passive"))
      (node (ref "C25") (pin "2") (pinfunction "2_2") (pintype "passive"))
      (node (ref "C3") (pin "2") (pinfunction "2_2") (pintype "passive"))
      (node (ref "C34") (pin "2") (pinfunction "2_2") (pintype "passive"))
      (node (ref "C37") (pin "2") (pinfunction "2_2") (pintype "passive"))
      (node (ref "C4") (pin "2") (pinfunction "2_2") (pintype "passive"))
      (node (ref "C40") (pin "2") (pinfunction "2_2") (pintype "passive"))
      (node (ref "C44") (pin "2") (pinfunction "2_2") (pintype "passive"))
      (node (ref "C47") (pin "2") (pinfunction "2_2") (pintype "passive"))
      (node (ref "C5") (pin "2") (pinfunction "2_2") (pintype "passive"))
      (node (ref "C51") (pin "1") (pinfunction "1_1") (pintype "passive"))
      (node (ref "C54") (pin "2") (pinfunction "2_2") (pintype "passive"))
      (node (ref "C55") (pin "2") (pinfunction "2_2") (pintype "passive"))
      (node (ref "C57") (pin "2") (pintype "passive"))
      (node (ref "C58") (pin "2") (pinfunction "2_2") (pintype "passive"))
      (node (ref "C7") (pin "2") (pinfunction "2_2") (pintype "passive"))
      (node (ref "C9") (pin "2") (pinfunction "2_2") (pintype "passive"))
      (node (ref "J3") (pin "2") (pinfunction "2_2") (pintype "passive"))
      (node (ref "J4") (pin "1") (pinfunction "1_1") (pintype "passive"))
      (node (ref "J5") (pin "3") (pinfunction "3_3") (pintype "passive"))
      (node (ref "P5") (pin "1") (pinfunction "1_1") (pintype "passive"))
      (node (ref "Q14") (pin "2") (pinfunction "E_2") (pintype "passive"))
      (node (ref "Q17") (pin "2") (pinfunction "E_2") (pintype "passive"))
      (node (ref "Q18") (pin "2") (pinfunction "E_2") (pintype "passive"))
      (node (ref "R52") (pin "1") (pinfunction "1_1") (pintype "passive"))
      (node (ref "R56") (pin "2") (pinfunction "2_2") (pintype "passive"))
      (node (ref "R58") (pin "1") (pinfunction "1_1") (pintype "passive"))
      (node (ref "R60") (pin "2") (pintype "passive"))
      (node (ref "S2") (pin "2") (pintype "passive"))
      (node (ref "TP5") (pin "1") (pinfunction "1_1") (pintype "passive"))
      (node (ref "TP6") (pin "1") (pinfunction "1_1") (pintype "passive"))
      (node (ref "U2") (pin "1") (pinfunction "GND_1") (pintype "passive"))
      (node (ref "U21") (pin "1") (pinfunction "GND_1") (pintype "passive"))
      (node (ref "U21") (pin "27") (pinfunction "GND_27") (pintype "passive"))
      (node (ref "U21") (pin "34") (pinfunction "GND_34") (pintype "passive"))
      (node (ref "U21") (pin "36") (pinfunction "GND_36") (pintype "passive"))
      (node (ref "U21") (pin "37") (pinfunction "GND_37") (pintype "passive"))
      (node (ref "U21") (pin "40") (pinfunction "GND_40") (pintype "passive"))
      (node (ref "U21") (pin "41") (pinfunction "GND_41") (pintype "passive"))
      (node (ref "U22") (pin "1") (pinfunction "GND_1") (pintype "passive"))
      (node (ref "U22") (pin "15") (pinfunction "GND_15") (pintype "passive"))
      (node (ref "U3") (pin "1") (pinfunction "GND_1") (pintype "passive"))
      (node (ref "U4") (pin "1") (pinfunction "GND_1") (pintype "passive"))
      (node (ref "U5") (pin "4") (pinfunction "GND_4") (pintype "passive"))
      (node (ref "U5") (pin "9") (pinfunction "Pad_9") (pintype "passive"))
      (node (ref "U8") (pin "1") (pinfunction "GND_1") (pintype "passive"))
      (node (ref "W1") (pin "2") (pinfunction "GND_2") (pintype "passive"))
    )
    (net (code "38") (name "GPRS_3.6V") (class "Default")
      (node (ref "C16") (pin "1") (pinfunction "1_1") (pintype "passive"))
      (node (ref "C17") (pin "1") (pinfunction "1_1") (pintype "passive"))
      (node (ref "C18") (pin "1") (pinfunction "1_1") (pintype "passive"))
      (node (ref "C37") (pin "1") (pinfunction "1_1") (pintype "passive"))
      (node (ref "C9") (pin "1") (pinfunction "1_1") (pintype "passive"))
      (node (ref "Q4") (pin "3") (pinfunction "D_3") (pintype "passive"))
      (node (ref "U21") (pin "42") (pinfunction "VBAT_42") (pintype "passive"))
      (node (ref "U21") (pin "43") (pinfunction "VBAT_43") (pintype "passive"))
    )
    (net (code "39") (name "Net-(C44-Pad1)") (class "Default")
      (node (ref "C44") (pin "1") (pinfunction "1_1") (pintype "passive"))
      (node (ref "C6") (pin "2") (pinfunction "2_2") (pintype "passive"))
    )
    (net (code "40") (name "Net-(J5-Pad1)") (class "Default")
      (node (ref "J5") (pin "1") (pinfunction "1_1") (pintype "passive"))
      (node (ref "J5") (pin "5") (pinfunction "5_5") (pintype "passive"))
      (node (ref "R61") (pin "2") (pintype "passive"))
    )
    (net (code "41") (name "Net-(Q1-G)") (class "Default")
      (node (ref "Q1") (pin "1") (pinfunction "G_1") (pintype "passive"))
      (node (ref "R15") (pin "2") (pinfunction "2_2") (pintype "passive"))
      (node (ref "R17") (pin "2") (pinfunction "2_2") (pintype "passive"))
    )
    (net (code "42") (name "Net-(Q2-B)") (class "Default")
      (node (ref "Q2") (pin "1") (pinfunction "B_1") (pintype "passive"))
      (node (ref "R44") (pin "2") (pinfunction "2_2") (pintype "passive"))
    )
    (net (code "43") (name "Net-(Q2-C)") (class "Default")
      (node (ref "C34") (pin "1") (pinfunction "1_1") (pintype "passive"))
      (node (ref "Q2") (pin "3") (pinfunction "C_3") (pintype "passive"))
      (node (ref "R45") (pin "1") (pinfunction "1_1") (pintype "passive"))
      (node (ref "U8") (pin "8") (pinfunction "VCC_8") (pintype "passive"))
    )
    (net (code "44") (name "Net-(Q3-D)") (class "Default")
      (node (ref "C6") (pin "1") (pinfunction "1_1") (pintype "passive"))
      (node (ref "Q3") (pin "3") (pinfunction "D_3") (pintype "passive"))
      (node (ref "R63") (pin "2") (pintype "passive"))
    )
    (net (code "45") (name "Net-(Q3-G)") (class "Default")
      (node (ref "C57") (pin "1") (pintype "passive"))
      (node (ref "Q3") (pin "1") (pinfunction "G_1") (pintype "passive"))
      (node (ref "R60") (pin "1") (pintype "passive"))
      (node (ref "R61") (pin "1") (pintype "passive"))
    )
    (net (code "46") (name "Net-(Q4-G)") (class "Default")
      (node (ref "Q4") (pin "1") (pinfunction "G_1") (pintype "passive"))
      (node (ref "R16") (pin "1") (pinfunction "1_1") (pintype "passive"))
      (node (ref "R18") (pin "2") (pinfunction "2_2") (pintype "passive"))
    )
    (net (code "47") (name "Net-(Q4-S)") (class "Default")
      (node (ref "C40") (pin "1") (pinfunction "1_1") (pintype "passive"))
      (node (ref "Q4") (pin "2") (pinfunction "S_2") (pintype "passive"))
      (node (ref "R16") (pin "2") (pinfunction "2_2") (pintype "passive"))
      (node (ref "R50") (pin "2") (pinfunction "2_2") (pintype "passive"))
      (node (ref "U4") (pin "3") (pinfunction "Vout_3") (pintype "passive"))
    )
    (net (code "48") (name "Net-(Q13-B)") (class "Default")
      (node (ref "Q13") (pin "1") (pinfunction "B_1") (pintype "passive"))
      (node (ref "R55") (pin "2") (pinfunction "2_2") (pintype "passive"))
    )
    (net (code "49") (name "Net-(Q13-C)") (class "Default")
      (node (ref "Q13") (pin "3") (pinfunction "C_3") (pintype "passive"))
      (node (ref "R9") (pin "1") (pinfunction "1_1") (pintype "passive"))
    )
    (net (code "50") (name "Net-(Q14-B)") (class "Default")
      (node (ref "Q14") (pin "1") (pinfunction "B_1") (pintype "passive"))
      (node (ref "R14") (pin "2") (pinfunction "2_2") (pintype "passive"))
    )
    (net (code "51") (name "Net-(Q14-C)") (class "Default")
      (node (ref "Q14") (pin "3") (pinfunction "C_3") (pintype "passive"))
      (node (ref "R10") (pin "1") (pinfunction "1_1") (pintype "passive"))
      (node (ref "R55") (pin "1") (pinfunction "1_1") (pintype "passive"))
    )
    (net (code "52") (name "Net-(Q17-B)") (class "Default")
      (node (ref "Q17") (pin "1") (pinfunction "B_1") (pintype "passive"))
      (node (ref "R51") (pin "2") (pinfunction "2_2") (pintype "passive"))
      (node (ref "R52") (pin "2") (pinfunction "2_2") (pintype "passive"))
    )
    (net (code "53") (name "Net-(Q18-B)") (class "Default")
      (node (ref "Q18") (pin "1") (pinfunction "B_1") (pintype "passive"))
      (node (ref "R57") (pin "2") (pinfunction "2_2") (pintype "passive"))
      (node (ref "R58") (pin "2") (pinfunction "2_2") (pintype "passive"))
    )
    (net (code "54") (name "Net-(U21A-ANT_RF)") (class "Default")
      (node (ref "C2") (pin "2") (pinfunction "2_2") (pintype "passive"))
      (node (ref "R2") (pin "2") (pinfunction "2_2") (pintype "passive"))
      (node (ref "U21") (pin "35") (pinfunction "ANT_RF_35") (pintype "passive"))
    )
    (net (code "55") (name "Net-(W1-ANT)") (class "Default")
      (node (ref "C1") (pin "2") (pinfunction "2_2") (pintype "passive"))
      (node (ref "R2") (pin "1") (pinfunction "1_1") (pintype "passive"))
      (node (ref "W1") (pin "1") (pinfunction "ANT_1") (pintype "passive"))
    )
    (net (code "56") (name "USIM_GND") (class "Default")
      (node (ref "C11") (pin "2") (pinfunction "2_2") (pintype "passive"))
      (node (ref "C12") (pin "2") (pinfunction "2_2") (pintype "passive"))
      (node (ref "SIM1") (pin "1") (pinfunction "VSS_1") (pintype "passive"))
      (node (ref "U21") (pin "10") (pinfunction "USIM_GND_10") (pintype "passive"))
    )
    (net (code "57") (name "USIM_VDD") (class "Default")
      (node (ref "C11") (pin "1") (pinfunction "1_1") (pintype "passive"))
      (node (ref "C12") (pin "1") (pinfunction "1_1") (pintype "passive"))
      (node (ref "SIM1") (pin "8") (pinfunction "VDD_8") (pintype "passive"))
      (node (ref "U21") (pin "14") (pinfunction "USIM_VDD_14") (pintype "passive"))
    )
    (net (code "58") (name "VDD_BLE") (class "Default")
      (node (ref "C13") (pin "1") (pinfunction "1_1") (pintype "passive"))
      (node (ref "C15") (pin "1") (pinfunction "1_1") (pintype "passive"))
      (node (ref "Q1") (pin "3") (pinfunction "D_3") (pintype "passive"))
      (node (ref "U22") (pin "14") (pinfunction "VDD_14") (pintype "passive"))
    )
    (net (code "59") (name "VDD_EXT_3V") (class "Default")
      (node (ref "C25") (pin "1") (pinfunction "1_1") (pintype "passive"))
      (node (ref "R24") (pin "1") (pinfunction "1_1") (pintype "passive"))
      (node (ref "U21") (pin "24") (pinfunction "VDD_EXT_24") (pintype "passive"))
    )
    (net (code "60") (name "VIN_N") (class "Default")
      (node (ref "C14") (pin "1") (pinfunction "1_1") (pintype "passive"))
      (node (ref "C47") (pin "1") (pinfunction "1_1") (pintype "passive"))
      (node (ref "C7") (pin "1") (pinfunction "1_1") (pintype "passive"))
      (node (ref "D11") (pin "2") (pinfunction "2_2") (pintype "passive"))
      (node (ref "D2") (pin "2") (pinfunction "2_2") (pintype "passive"))
      (node (ref "R30") (pin "1") (pinfunction "1_1") (pintype "passive"))
      (node (ref "R50") (pin "1") (pinfunction "1_1") (pintype "passive"))
      (node (ref "U2") (pin "2") (pinfunction "Vin_2") (pintype "passive"))
      (node (ref "U4") (pin "2") (pinfunction "Vin_2") (pintype "passive"))
    )
    (net (code "61") (name "VRTC") (class "Default")
      (node (ref "C10") (pin "1") (pinfunction "1_1") (pintype "passive"))
      (node (ref "J3") (pin "1") (pinfunction "1_1") (pintype "passive"))
      (node (ref "TP7") (pin "1") (pinfunction "1_1") (pintype "passive"))
    )
    (net (code "62") (name "Vin") (class "Default")
      (node (ref "D2") (pin "1") (pinfunction "1_1") (pintype "passive"))
      (node (ref "J4") (pin "2") (pinfunction "2_2") (pintype "passive"))
      (node (ref "Q13") (pin "2") (pinfunction "E_2") (pintype "passive"))
      (node (ref "R10") (pin "2") (pinfunction "2_2") (pintype "passive"))
      (node (ref "TP1") (pin "1") (pinfunction "1_1") (pintype "passive"))
    )
    (net (code "63") (name "unconnected-(SIM1-NC-Pad4)") (class "Default")
      (node (ref "SIM1") (pin "4") (pinfunction "NC_4") (pintype "passive"))
    )
    (net (code "64") (name "unconnected-(SIM1-NC-Pad5)") (class "Default")
      (node (ref "SIM1") (pin "5") (pinfunction "NC_5") (pintype "passive"))
    )
    (net (code "65") (name "unconnected-(U8-NC-Pad2)") (class "Default")
      (node (ref "U8") (pin "2") (pinfunction "NC_2") (pintype "passive"))
    )
    (net (code "66") (name "unconnected-(U8-NC-Pad4)") (class "Default")
      (node (ref "U8") (pin "4") (pinfunction "NC_4") (pintype "passive"))
    )
    (net (code "67") (name "unconnected-(U8-NC-Pad5)") (class "Default")
      (node (ref "U8") (pin "5") (pinfunction "NC_5") (pintype "passive"))
    )
    (net (code "68") (name "unconnected-(U21A-ADC-Pad9)") (class "Default")
      (node (ref "U21") (pin "9") (pinfunction "ADC_9") (pintype "passive+no_connect"))
    )
    (net (code "69") (name "unconnected-(U21A-BOOT-Pad7)") (class "Default")
      (node (ref "U21") (pin "7") (pinfunction "BOOT_7") (pintype "passive+no_connect"))
    )
    (net (code "70") (name "unconnected-(U21A-NET_STATUS-Pad16)") (class "Default")
      (node (ref "U21") (pin "16") (pinfunction "NET_STATUS_16") (pintype "passive+no_connect"))
    )
    (net (code "71") (name "unconnected-(U21A-RESERVED-Pad2)") (class "Default")
      (node (ref "U21") (pin "2") (pinfunction "RESERVED_2") (pintype "passive+no_connect"))
    )
    (net (code "72") (name "unconnected-(U21A-RESERVED-Pad3)") (class "Default")
      (node (ref "U21") (pin "3") (pinfunction "RESERVED_3") (pintype "passive+no_connect"))
    )
    (net (code "73") (name "unconnected-(U21A-RESERVED-Pad4)") (class "Default")
      (node (ref "U21") (pin "4") (pinfunction "RESERVED_4") (pintype "passive+no_connect"))
    )
    (net (code "74") (name "unconnected-(U21A-RESERVED-Pad5)") (class "Default")
      (node (ref "U21") (pin "5") (pinfunction "RESERVED_5") (pintype "passive+no_connect"))
    )
    (net (code "75") (name "unconnected-(U21A-RESERVED-Pad6)") (class "Default")
      (node (ref "U21") (pin "6") (pinfunction "RESERVED_6") (pintype "passive+no_connect"))
    )
    (net (code "76") (name "unconnected-(U21A-RESERVED-Pad8)") (class "Default")
      (node (ref "U21") (pin "8") (pinfunction "RESERVED_8") (pintype "passive+no_connect"))
    )
    (net (code "77") (name "unconnected-(U21A-RESERVED-Pad21)") (class "Default")
      (node (ref "U21") (pin "21") (pinfunction "RESERVED_21") (pintype "passive+no_connect"))
    )
    (net (code "78") (name "unconnected-(U21A-RESERVED-Pad22)") (class "Default")
      (node (ref "U21") (pin "22") (pinfunction "RESERVED_22") (pintype "passive+no_connect"))
    )
    (net (code "79") (name "unconnected-(U21A-RESERVED-Pad23)") (class "Default")
      (node (ref "U21") (pin "23") (pinfunction "RESERVED_23") (pintype "passive+no_connect"))
    )
    (net (code "80") (name "unconnected-(U21A-RESERVED-Pad25)") (class "Default")
      (node (ref "U21") (pin "25") (pinfunction "RESERVED_25") (pintype "passive+no_connect"))
    )
    (net (code "81") (name "unconnected-(U21A-RESERVED-Pad26)") (class "Default")
      (node (ref "U21") (pin "26") (pinfunction "RESERVED_26") (pintype "passive+no_connect"))
    )
    (net (code "82") (name "unconnected-(U21A-RESERVED-Pad28)") (class "Default")
      (node (ref "U21") (pin "28") (pinfunction "RESERVED_28") (pintype "passive+no_connect"))
    )
    (net (code "83") (name "unconnected-(U21A-RESERVED-Pad29)") (class "Default")
      (node (ref "U21") (pin "29") (pinfunction "RESERVED_29") (pintype "passive+no_connect"))
    )
    (net (code "84") (name "unconnected-(U21A-RESERVED-Pad30)") (class "Default")
      (node (ref "U21") (pin "30") (pinfunction "RESERVED_30") (pintype "passive+no_connect"))
    )
    (net (code "85") (name "unconnected-(U21A-RESERVED-Pad31)") (class "Default")
      (node (ref "U21") (pin "31") (pinfunction "RESERVED_31") (pintype "passive+no_connect"))
    )
    (net (code "86") (name "unconnected-(U21A-RESERVED-Pad32)") (class "Default")
      (node (ref "U21") (pin "32") (pinfunction "RESERVED_32") (pintype "passive+no_connect"))
    )
    (net (code "87") (name "unconnected-(U21A-RESERVED-Pad33)") (class "Default")
      (node (ref "U21") (pin "33") (pinfunction "RESERVED_33") (pintype "passive+no_connect"))
    )
    (net (code "88") (name "unconnected-(U21A-RESERVED-Pad44)") (class "Default")
      (node (ref "U21") (pin "44") (pinfunction "RESERVED_44") (pintype "passive+no_connect"))
    )
    (net (code "89") (name "unconnected-(U21A-RI-Pad20)") (class "Default")
      (node (ref "U21") (pin "20") (pinfunction "RI_20") (pintype "passive+no_connect"))
    )
    (net (code "90") (name "unconnected-(U21B-RESERVED-Pad45)") (class "Default")
      (node (ref "U21") (pin "45") (pinfunction "RESERVED_45") (pintype "passive+no_connect"))
    )
    (net (code "91") (name "unconnected-(U21B-RESERVED-Pad46)") (class "Default")
      (node (ref "U21") (pin "46") (pinfunction "RESERVED_46") (pintype "passive+no_connect"))
    )
    (net (code "92") (name "unconnected-(U21B-RESERVED-Pad47)") (class "Default")
      (node (ref "U21") (pin "47") (pinfunction "RESERVED_47") (pintype "passive+no_connect"))
    )
    (net (code "93") (name "unconnected-(U21B-RESERVED-Pad48)") (class "Default")
      (node (ref "U21") (pin "48") (pinfunction "RESERVED_48") (pintype "passive+no_connect"))
    )
    (net (code "94") (name "unconnected-(U21B-RESERVED-Pad49)") (class "Default")
      (node (ref "U21") (pin "49") (pinfunction "RESERVED_49") (pintype "passive+no_connect"))
    )
    (net (code "95") (name "unconnected-(U21B-RESERVED-Pad50)") (class "Default")
      (node (ref "U21") (pin "50") (pinfunction "RESERVED_50") (pintype "passive+no_connect"))
    )
    (net (code "96") (name "unconnected-(U21B-RESERVED-Pad51)") (class "Default")
      (node (ref "U21") (pin "51") (pinfunction "RESERVED_51") (pintype "passive+no_connect"))
    )
    (net (code "97") (name "unconnected-(U21B-RESERVED-Pad52)") (class "Default")
      (node (ref "U21") (pin "52") (pinfunction "RESERVED_52") (pintype "passive+no_connect"))
    )
    (net (code "98") (name "unconnected-(U21B-RESERVED-Pad53)") (class "Default")
      (node (ref "U21") (pin "53") (pinfunction "RESERVED_53") (pintype "passive+no_connect"))
    )
    (net (code "99") (name "unconnected-(U21B-RESERVED-Pad54)") (class "Default")
      (node (ref "U21") (pin "54") (pinfunction "RESERVED_54") (pintype "passive+no_connect"))
    )
    (net (code "100") (name "unconnected-(U21B-RESERVED-Pad55)") (class "Default")
      (node (ref "U21") (pin "55") (pinfunction "RESERVED_55") (pintype "passive+no_connect"))
    )
    (net (code "101") (name "unconnected-(U21B-RESERVED-Pad56)") (class "Default")
      (node (ref "U21") (pin "56") (pinfunction "RESERVED_56") (pintype "passive+no_connect"))
    )
    (net (code "102") (name "unconnected-(U21B-RESERVED-Pad57)") (class "Default")
      (node (ref "U21") (pin "57") (pinfunction "RESERVED_57") (pintype "passive+no_connect"))
    )
    (net (code "103") (name "unconnected-(U21B-RESERVED-Pad58)") (class "Default")
      (node (ref "U21") (pin "58") (pinfunction "RESERVED_58") (pintype "passive+no_connect"))
    )
    (net (code "104") (name "unconnected-(U22-P0.00{slash}XL1-Pad13)") (class "Default")
      (node (ref "U22") (pin "13") (pinfunction "P0.00/XL1_13") (pintype "passive"))
    )
    (net (code "105") (name "unconnected-(U22-P0.01{slash}XL2-Pad12)") (class "Default")
      (node (ref "U22") (pin "12") (pinfunction "P0.01/XL2_12") (pintype "passive"))
    )
    (net (code "106") (name "unconnected-(U22-P0.04{slash}AIN2-Pad11)") (class "Default")
      (node (ref "U22") (pin "11") (pinfunction "P0.04/AIN2_11") (pintype "passive"))
    )
    (net (code "107") (name "unconnected-(U22-P0.16-Pad7)") (class "Default")
      (node (ref "U22") (pin "7") (pinfunction "P0.16_7") (pintype "passive"))
    )
    (net (code "108") (name "unconnected-(U22-P0.18-Pad6)") (class "Default")
      (node (ref "U22") (pin "6") (pinfunction "P0.18_6") (pintype "passive"))
    )
    (net (code "109") (name "unconnected-(U22-P0.20-Pad5)") (class "Default")
      (node (ref "U22") (pin "5") (pinfunction "P0.20_5") (pintype "passive"))
    )
    (net (code "110") (name "unconnected-(U22-SWCLK-Pad3)") (class "Default")
      (node (ref "U22") (pin "3") (pinfunction "SWCLK_3") (pintype "passive"))
    )
    (net (code "111") (name "unconnected-(U22-SWDIO-Pad2)") (class "Default")
      (node (ref "U22") (pin "2") (pinfunction "SWDIO_2") (pintype "passive"))
    )
    (net (code "112") (name "unconnected-(U22-nRESET-Pad4)") (class "Default")
      (node (ref "U22") (pin "4") (pinfunction "nRESET_4") (pintype "passive"))
    )
  )
)
